# working.net
KiCad netlist of a schematic drawn in EAGLE
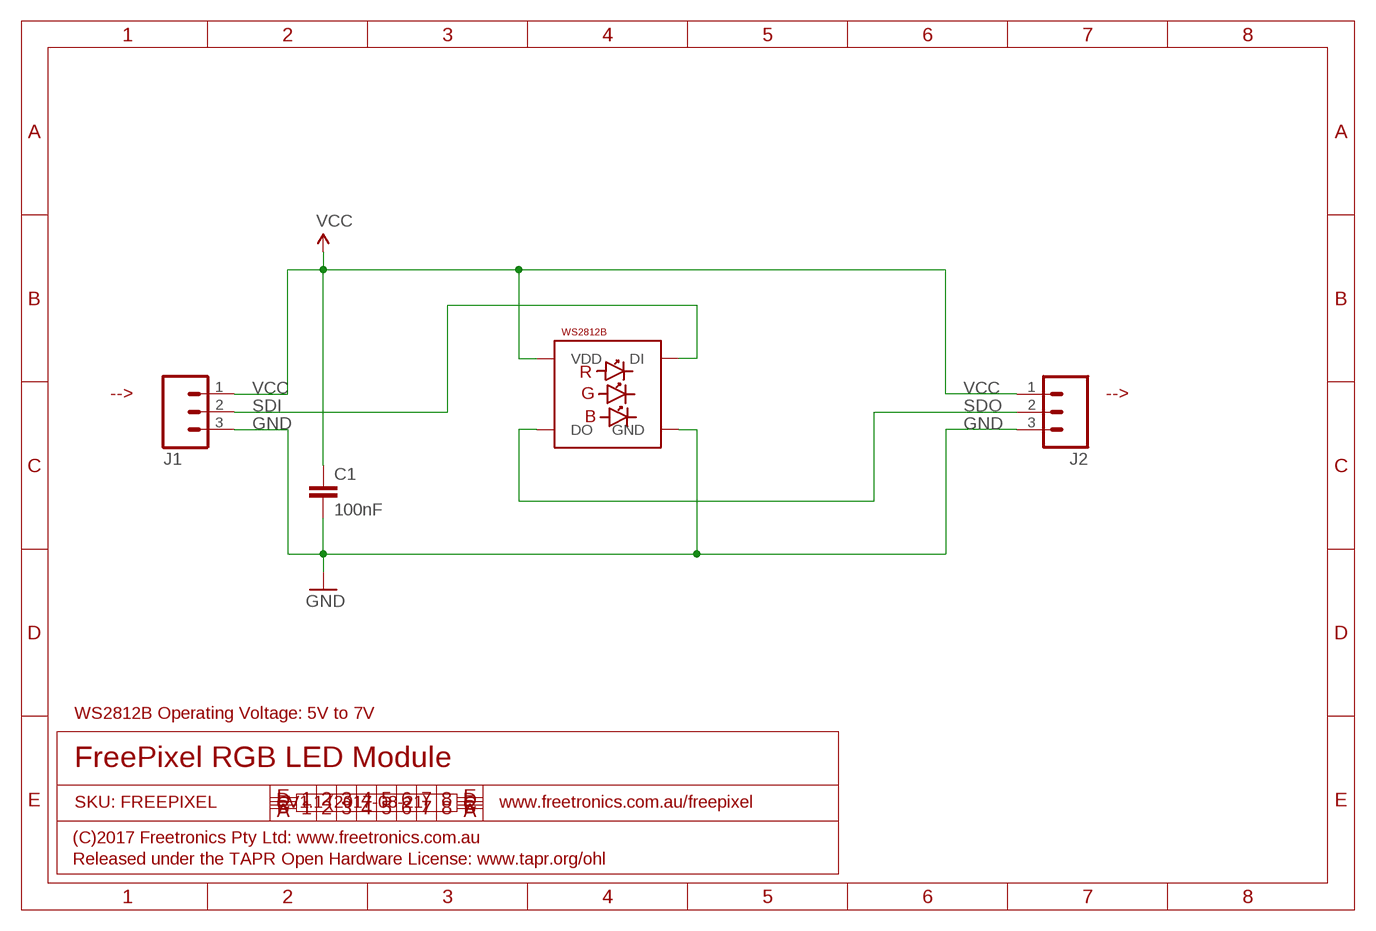
[diagram p0: schematic, sheet 1]

(export (version "E")
  (design (tool "Eeschema 10.0.6"))
  (components
    (comp (ref "C1")
      (value "100nF")
      (footprint "eagle-import:0603")
      (libsource (lib "eagle-import") (part "CAP0603"))
    )
    (comp (ref "J1")
      (value "M03PTH")
      (footprint "eagle-import:1X03")
      (libsource (lib "eagle-import") (part "M03PTH"))
    )
    (comp (ref "J2")
      (value "M03PTH")
      (footprint "eagle-import:1X03")
      (libsource (lib "eagle-import") (part "M03PTH"))
    )
    (comp (ref "LED1")
      (value "WS2812B5050")
      (footprint "eagle-import:WS2812B")
      (libsource (lib "eagle-import") (part "WS2812B5050"))
    )
  )
  (nets
    (net (code "1") (name "/SDI") (class "Default")
      (node (ref "J1") (pin "2") (pinfunction "2_2") (pintype "passive"))
      (node (ref "LED1") (pin "4-DIN") (pinfunction "DI_4-DIN") (pintype "input"))
    )
    (net (code "2") (name "/SDO") (class "Default")
      (node (ref "J2") (pin "2") (pinfunction "2_2") (pintype "passive"))
      (node (ref "LED1") (pin "2-DOUT") (pinfunction "DO_2-DOUT") (pintype "output"))
    )
    (net (code "3") (name "GND") (class "Default")
      (node (ref "C1") (pin "2") (pinfunction "2_2") (pintype "passive"))
      (node (ref "J1") (pin "3") (pinfunction "3_3") (pintype "passive"))
      (node (ref "J2") (pin "3") (pinfunction "3_3") (pintype "passive"))
      (node (ref "LED1") (pin "3-GND") (pinfunction "GND_3-GND") (pintype "power_in"))
    )
    (net (code "4") (name "VCC") (class "Default")
      (node (ref "C1") (pin "1") (pinfunction "1_1") (pintype "passive"))
      (node (ref "J1") (pin "1") (pinfunction "1_1") (pintype "passive"))
      (node (ref "J2") (pin "1") (pinfunction "1_1") (pintype "passive"))
      (node (ref "LED1") (pin "1-VDD") (pinfunction "VDD_1-VDD") (pintype "power_in"))
    )
  )
)
